# Level_sensor.net
KiCad netlist of a schematic drawn in EAGLE
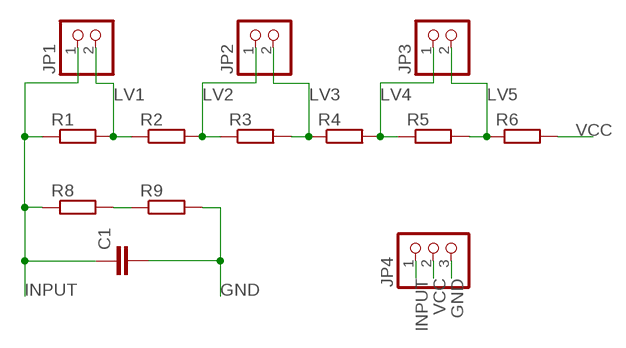
[diagram p0: schematic, sheet 1]

(export (version "E")
  (design (tool "Eeschema 10.0.6"))
  (components
    (comp (ref "C1")
      (value "C-EU025-030X050")
      (footprint "eagle-import:C025-030X050")
      (libsource (lib "eagle-import") (part "C-EU025-030X050"))
    )
    (comp (ref "JP1")
      (value "PINHD-1X2")
      (footprint "eagle-import:1X02")
      (libsource (lib "eagle-import") (part "PINHD-1X2"))
    )
    (comp (ref "JP2")
      (value "PINHD-1X2")
      (footprint "eagle-import:1X02")
      (libsource (lib "eagle-import") (part "PINHD-1X2"))
    )
    (comp (ref "JP3")
      (value "PINHD-1X2")
      (footprint "eagle-import:1X02")
      (libsource (lib "eagle-import") (part "PINHD-1X2"))
    )
    (comp (ref "JP4")
      (value "PINHD-1X3")
      (footprint "eagle-import:1X03")
      (libsource (lib "eagle-import") (part "PINHD-1X3"))
    )
    (comp (ref "R1")
      (value "R-EU_0204/7")
      (footprint "eagle-import:0204_7")
      (libsource (lib "eagle-import") (part "R-EU_0204/7"))
    )
    (comp (ref "R2")
      (value "R-EU_0204/7")
      (footprint "eagle-import:0204_7")
      (libsource (lib "eagle-import") (part "R-EU_0204/7"))
    )
    (comp (ref "R3")
      (value "R-EU_0204/7")
      (footprint "eagle-import:0204_7")
      (libsource (lib "eagle-import") (part "R-EU_0204/7"))
    )
    (comp (ref "R4")
      (value "R-EU_0204/7")
      (footprint "eagle-import:0204_7")
      (libsource (lib "eagle-import") (part "R-EU_0204/7"))
    )
    (comp (ref "R5")
      (value "R-EU_0204/7")
      (footprint "eagle-import:0204_7")
      (libsource (lib "eagle-import") (part "R-EU_0204/7"))
    )
    (comp (ref "R6")
      (value "R-EU_0204/7")
      (footprint "eagle-import:0204_7")
      (libsource (lib "eagle-import") (part "R-EU_0204/7"))
    )
    (comp (ref "R8")
      (value "R-EU_0204/7")
      (footprint "eagle-import:0204_7")
      (libsource (lib "eagle-import") (part "R-EU_0204/7"))
    )
    (comp (ref "R9")
      (value "R-EU_0204/7")
      (footprint "eagle-import:0204_7")
      (libsource (lib "eagle-import") (part "R-EU_0204/7"))
    )
  )
  (nets
    (net (code "1") (name "/GND") (class "Default")
      (node (ref "C1") (pin "2") (pinfunction "2_2") (pintype "passive"))
      (node (ref "JP4") (pin "3") (pinfunction "3_3") (pintype "passive"))
      (node (ref "R9") (pin "2") (pinfunction "2_2") (pintype "passive"))
    )
    (net (code "2") (name "/INPUT") (class "Default")
      (node (ref "C1") (pin "1") (pinfunction "1_1") (pintype "passive"))
      (node (ref "JP1") (pin "1") (pinfunction "1_1") (pintype "passive"))
      (node (ref "JP4") (pin "1") (pinfunction "1_1") (pintype "passive"))
      (node (ref "R1") (pin "1") (pinfunction "1_1") (pintype "passive"))
      (node (ref "R8") (pin "1") (pinfunction "1_1") (pintype "passive"))
    )
    (net (code "3") (name "/LV1") (class "Default")
      (node (ref "JP1") (pin "2") (pinfunction "2_2") (pintype "passive"))
      (node (ref "R1") (pin "2") (pinfunction "2_2") (pintype "passive"))
      (node (ref "R2") (pin "1") (pinfunction "1_1") (pintype "passive"))
    )
    (net (code "4") (name "/LV2") (class "Default")
      (node (ref "JP2") (pin "1") (pinfunction "1_1") (pintype "passive"))
      (node (ref "R2") (pin "2") (pinfunction "2_2") (pintype "passive"))
      (node (ref "R3") (pin "1") (pinfunction "1_1") (pintype "passive"))
    )
    (net (code "5") (name "/LV3") (class "Default")
      (node (ref "JP2") (pin "2") (pinfunction "2_2") (pintype "passive"))
      (node (ref "R3") (pin "2") (pinfunction "2_2") (pintype "passive"))
      (node (ref "R4") (pin "1") (pinfunction "1_1") (pintype "passive"))
    )
    (net (code "6") (name "/LV4") (class "Default")
      (node (ref "JP3") (pin "1") (pinfunction "1_1") (pintype "passive"))
      (node (ref "R4") (pin "2") (pinfunction "2_2") (pintype "passive"))
      (node (ref "R5") (pin "1") (pinfunction "1_1") (pintype "passive"))
    )
    (net (code "7") (name "/LV5") (class "Default")
      (node (ref "JP3") (pin "2") (pinfunction "2_2") (pintype "passive"))
      (node (ref "R5") (pin "2") (pinfunction "2_2") (pintype "passive"))
      (node (ref "R6") (pin "1") (pinfunction "1_1") (pintype "passive"))
    )
    (net (code "8") (name "/VCC") (class "Default")
      (node (ref "JP4") (pin "2") (pinfunction "2_2") (pintype "passive"))
      (node (ref "R6") (pin "2") (pinfunction "2_2") (pintype "passive"))
    )
    (net (code "9") (name "Net-(R8-Pad2)") (class "Default")
      (node (ref "R8") (pin "2") (pinfunction "2_2") (pintype "passive"))
      (node (ref "R9") (pin "1") (pinfunction "1_1") (pintype "passive"))
    )
  )
)
